# LNBF.net
KiCad netlist of a schematic drawn in Altium Designer
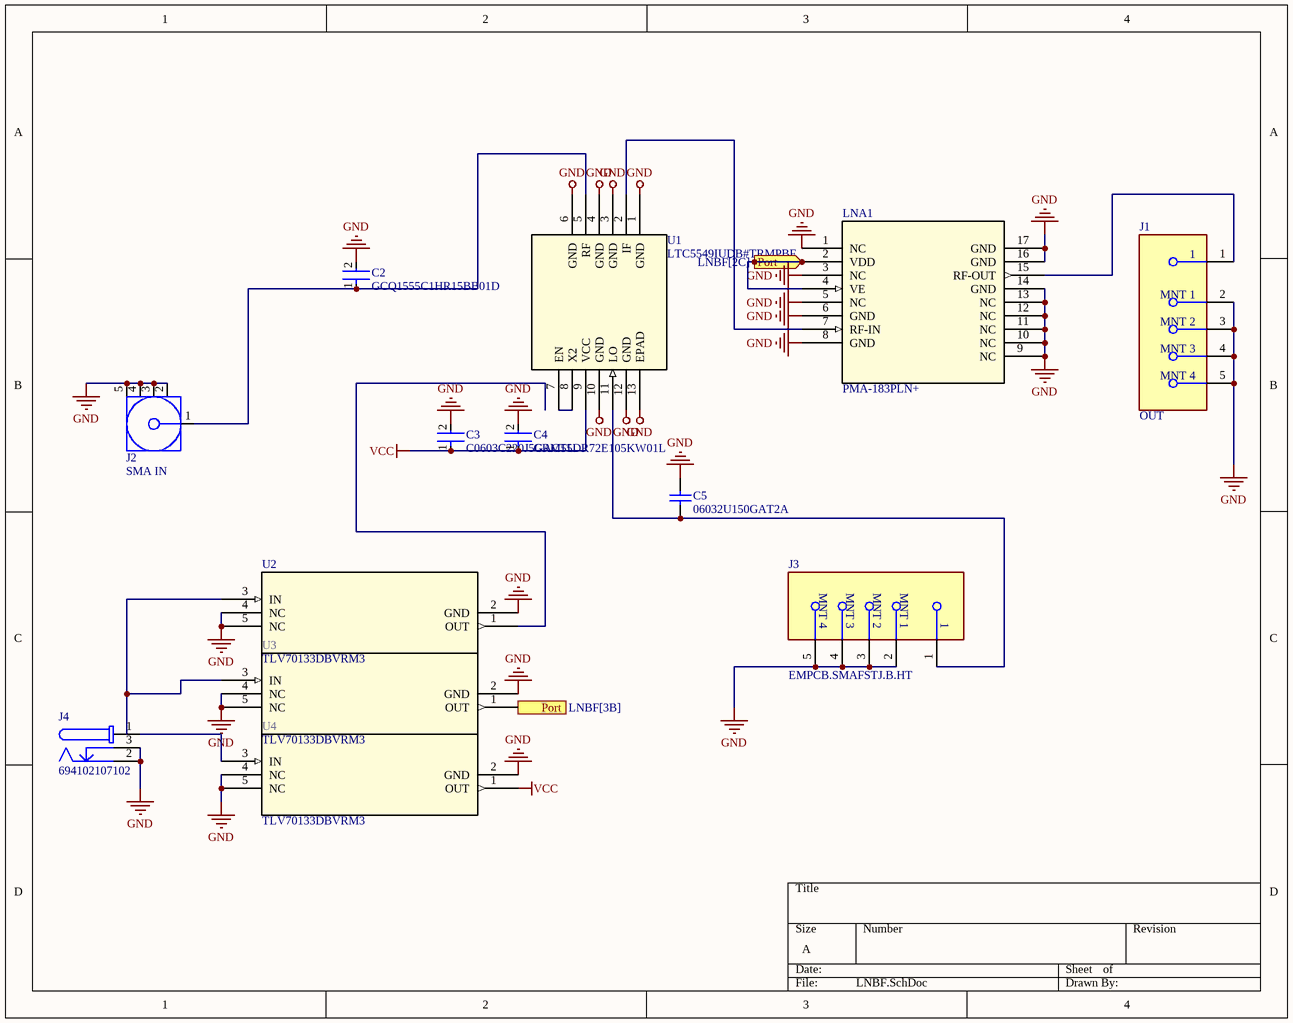
[diagram p0: LNBF.SchDoc]

(export (version "E")
  (design (tool "Eeschema 10.0.6"))
  (components
    (comp (ref "C2")
      (value "GCQ1555C1HR15BB01D")
      (footprint "FP-GCQ155-0_05-MFG")
      (description "High Q Ceramic Capacitor for Automotive 0.15pF ±0.1pF 50VDC C0G 0402 Paper T/R")
      (libsource (lib "Altium Content Vault") (part "02cd4be3c70576c341d710602a673aa"))
    )
    (comp (ref "C3")
      (value "C0603C220J5GACTU")
      (footprint "FP-C0603C-CF-MFG")
      (description "Cap Ceramic 22pF 50V C0G 5% SMD 0603 125°C Paper T/R")
      (fields (field (name "TOLERANCE") "0.05") (field (name "MANUFACTURER") "KEMET"))
      (libsource (lib "Altium Content Vault") (part "b4654b650e69147ec39a6b967a45e02"))
    )
    (comp (ref "C4")
      (value "GRM55DR72E105KW01L")
      (footprint "FP-GRM55D-0_4-IPC_A")
      (description "Chip Multilayer Ceramic Capacitors for General Purpose, 2220, 1.0uF, X7R, 15%, 10%, 250V")
      (fields (field (name "VOLTAGE") "250V") (field (name "TOLERANCE") "10%"))
      (libsource (lib "Altium Content Vault") (part "b4654b650e69147ec39a6b967a45e02"))
    )
    (comp (ref "C5")
      (value "06032U150GAT2A")
      (footprint "CAPC1508X91X25LL25T13")
      (fields (field (name "MANUFACTURER") "AVX Interconnect / Elco"))
      (libsource (lib "Altium Content Vault") (part "CAP"))
    )
    (comp (ref "J1")
      (value "OUT")
      (footprint "FP-EMPCB_SMAFSTJ_B_HT-MFG")
      (description "CONN SMA JACK STR 50OHM EDGE MNT")
      (fields
        (field (name "OCTOPART") "https://octopart.com/empcb.smafstj.b.ht-taoglas-24204431")
        (field (name "MANUFACTURER PART NUMBER") "EMPCB.SMAFSTJ.B.HT")
      )
      (libsource (lib "") (part "c65b8a639cdaef1819ea20b5466f8fa_1"))
    )
    (comp (ref "J2")
      (value "SMA IN")
      (footprint "MOLX-731000114_V")
      (description "SMA Right-Angle PCB Jack Receptacle, Brass Body, Gold Plated, 50 Ohm, 5-Pin THD, RoHS, Tray")
      (fields (field (name "MANUFACTURER") "Molex"))
      (libsource (lib "Altium Content Vault") (part "CN-S-4F-RF5"))
    )
    (comp (ref "J3")
      (value "EMPCB.SMAFSTJ.B.HT")
      (footprint "FP-EMPCB_SMAFSTJ_B_HT-MFG")
      (description "CONN SMA JACK STR 50OHM EDGE MNT")
      (fields
        (field (name "OCTOPART") "https://octopart.com/empcb.smafstj.b.ht-taoglas-24204431")
        (field (name "MANUFACTURER") "Taoglas Limited")
      )
      (libsource (lib "Altium Content Vault") (part "c65b8a639cdaef1819ea20b5466f8fa"))
    )
    (comp (ref "J4")
      (value "694102107102")
      (footprint "694102107102")
      (libsource (lib "Altium Content Vault") (part "DC Power Jack"))
    )
    (comp (ref "LNA1")
      (value "PMA-183PLN+")
      (footprint "JV2579_MNC")
      (description "No Description Available")
      (fields (field (name "COPYRIGHT") "Copyright (C) 2024 Ultra Librarian. All rights reserved."))
      (libsource (lib "PMA-183PLN&plus_") (part "PMA-183PLN+"))
    )
    (comp (ref "U1")
      (value "LTC5549IUDB#TRMPBF")
      (footprint "LTC5549IUDBTRMPBF_ADI")
      (description "No Description Available")
      (fields (field (name "COPYRIGHT") "Copyright (C) 2024 Ultra Librarian. All rights reserved."))
      (libsource (lib "LTC5549IUDBTRMPBF") (part "LTC5549IUDBTRMPBF"))
    )
    (comp (ref "U2")
      (value "TLV70133DBVRM3")
      (footprint "DBV5")
      (description "No Description Available")
      (fields (field (name "COPYRIGHT") "Copyright (C) 2024 Ultra Librarian. All rights reserved."))
      (libsource (lib "TLV70133DBVRM3") (part "TLV70133DBVRM3"))
    )
    (comp (ref "U3")
      (value "TLV70133DBVRM3")
      (footprint "DBV5")
      (description "No Description Available")
      (fields (field (name "COPYRIGHT") "Copyright (C) 2024 Ultra Librarian. All rights reserved."))
      (libsource (lib "TLV70133DBVRM3") (part "TLV70133DBVRM3"))
    )
    (comp (ref "U4")
      (value "TLV70133DBVRM3")
      (footprint "DBV5")
      (description "No Description Available")
      (fields (field (name "COPYRIGHT") "Copyright (C) 2024 Ultra Librarian. All rights reserved."))
      (libsource (lib "TLV70133DBVRM3") (part "TLV70133DBVRM3"))
    )
  )
  (nets
    (net (code "1") (name "/Port") (class "Default")
      (node (ref "LNA1") (pin "2") (pinfunction "VDD_2") (pintype "power_in"))
      (node (ref "LNA1") (pin "4") (pinfunction "VE_4") (pintype "input"))
      (node (ref "U3") (pin "1") (pinfunction "OUT_1") (pintype "output"))
    )
    (net (code "2") (name "GND") (class "Default")
      (node (ref "C2") (pin "2") (pinfunction "2_2") (pintype "passive"))
      (node (ref "C3") (pin "2") (pinfunction "2_2") (pintype "passive"))
      (node (ref "C4") (pin "2") (pinfunction "2_2") (pintype "passive"))
      (node (ref "C5") (pin "1") (pinfunction "1_1") (pintype "passive"))
      (node (ref "J1") (pin "2") (pinfunction "MNT_1_2") (pintype "passive"))
      (node (ref "J1") (pin "3") (pinfunction "MNT_2_3") (pintype "passive"))
      (node (ref "J1") (pin "4") (pinfunction "MNT_3_4") (pintype "passive"))
      (node (ref "J1") (pin "5") (pinfunction "MNT_4_5") (pintype "passive"))
      (node (ref "J2") (pin "2") (pinfunction "2_2") (pintype "passive"))
      (node (ref "J2") (pin "3") (pinfunction "3_3") (pintype "passive"))
      (node (ref "J2") (pin "4") (pinfunction "4_4") (pintype "passive"))
      (node (ref "J2") (pin "5") (pinfunction "5_5") (pintype "passive"))
      (node (ref "J3") (pin "2") (pinfunction "MNT_1_2") (pintype "passive"))
      (node (ref "J3") (pin "3") (pinfunction "MNT_2_3") (pintype "passive"))
      (node (ref "J3") (pin "4") (pinfunction "MNT_3_4") (pintype "passive"))
      (node (ref "J3") (pin "5") (pinfunction "MNT_4_5") (pintype "passive"))
      (node (ref "J4") (pin "2") (pinfunction "2_2") (pintype "passive"))
      (node (ref "J4") (pin "3") (pinfunction "3_3") (pintype "passive"))
      (node (ref "LNA1") (pin "1") (pinfunction "NC_1") (pintype "passive"))
      (node (ref "LNA1") (pin "10") (pinfunction "NC_10") (pintype "passive"))
      (node (ref "LNA1") (pin "11") (pinfunction "NC_11") (pintype "passive"))
      (node (ref "LNA1") (pin "12") (pinfunction "NC_12") (pintype "passive"))
      (node (ref "LNA1") (pin "13") (pinfunction "NC_13") (pintype "passive"))
      (node (ref "LNA1") (pin "14") (pinfunction "GND_14") (pintype "power_in"))
      (node (ref "LNA1") (pin "16") (pinfunction "GND_16") (pintype "power_in"))
      (node (ref "LNA1") (pin "17") (pinfunction "GND_17") (pintype "power_in"))
      (node (ref "LNA1") (pin "3") (pinfunction "NC_3") (pintype "passive"))
      (node (ref "LNA1") (pin "5") (pinfunction "NC_5") (pintype "passive"))
      (node (ref "LNA1") (pin "6") (pinfunction "GND_6") (pintype "power_in"))
      (node (ref "LNA1") (pin "8") (pinfunction "GND_8") (pintype "power_in"))
      (node (ref "LNA1") (pin "9") (pinfunction "NC_9") (pintype "passive"))
      (node (ref "U1") (pin "1") (pinfunction "GND_1") (pintype "power_in"))
      (node (ref "U1") (pin "10") (pinfunction "GND_10") (pintype "power_in"))
      (node (ref "U1") (pin "12") (pinfunction "GND_12") (pintype "power_in"))
      (node (ref "U1") (pin "13") (pinfunction "EPAD_13") (pintype "power_in"))
      (node (ref "U1") (pin "3") (pinfunction "GND_3") (pintype "power_in"))
      (node (ref "U1") (pin "4") (pinfunction "GND_4") (pintype "power_in"))
      (node (ref "U1") (pin "6") (pinfunction "GND_6") (pintype "power_in"))
      (node (ref "U2") (pin "2") (pinfunction "GND_2") (pintype "power_in"))
      (node (ref "U2") (pin "4") (pinfunction "NC_4") (pintype "passive"))
      (node (ref "U2") (pin "5") (pinfunction "NC_5") (pintype "passive"))
      (node (ref "U3") (pin "2") (pinfunction "GND_2") (pintype "power_in"))
      (node (ref "U3") (pin "4") (pinfunction "NC_4") (pintype "passive"))
      (node (ref "U3") (pin "5") (pinfunction "NC_5") (pintype "passive"))
      (node (ref "U4") (pin "2") (pinfunction "GND_2") (pintype "power_in"))
      (node (ref "U4") (pin "4") (pinfunction "NC_4") (pintype "passive"))
      (node (ref "U4") (pin "5") (pinfunction "NC_5") (pintype "passive"))
    )
    (net (code "3") (name "Net-(LNA1-RF-IN)") (class "Default")
      (node (ref "LNA1") (pin "7") (pinfunction "RF-IN_7") (pintype "input"))
      (node (ref "U1") (pin "2") (pinfunction "IF_2") (pintype "passive"))
    )
    (net (code "4") (name "Net-(LNA1-RF-OUT)") (class "Default")
      (node (ref "J1") (pin "1") (pinfunction "1_1") (pintype "passive"))
      (node (ref "LNA1") (pin "15") (pinfunction "RF-OUT_15") (pintype "output"))
    )
    (net (code "5") (name "Net-(U1-EN)") (class "Default")
      (node (ref "U1") (pin "7") (pinfunction "EN_7") (pintype "passive"))
      (node (ref "U1") (pin "8") (pinfunction "X2_8") (pintype "passive"))
    )
    (net (code "6") (name "Net-(U1-LO)") (class "Default")
      (node (ref "C5") (pin "2") (pinfunction "2_2") (pintype "passive"))
      (node (ref "J3") (pin "1") (pinfunction "1_1") (pintype "passive"))
      (node (ref "U1") (pin "11") (pinfunction "LO_11") (pintype "input"))
    )
    (net (code "7") (name "Net-(U1-RF)") (class "Default")
      (node (ref "C2") (pin "1") (pinfunction "1_1") (pintype "passive"))
      (node (ref "J2") (pin "1") (pinfunction "1_1") (pintype "passive"))
      (node (ref "U1") (pin "5") (pinfunction "RF_5") (pintype "passive"))
    )
    (net (code "8") (name "Net-(U2-IN)") (class "Default")
      (node (ref "U2") (pin "3") (pinfunction "IN_3") (pintype "input"))
      (node (ref "U3") (pin "3") (pinfunction "IN_3") (pintype "input"))
    )
    (net (code "9") (name "Net-(U4-IN)") (class "Default")
      (node (ref "J4") (pin "1") (pinfunction "1_1") (pintype "passive"))
      (node (ref "U4") (pin "3") (pinfunction "IN_3") (pintype "input"))
    )
    (net (code "10") (name "VCC") (class "Default")
      (node (ref "C3") (pin "1") (pinfunction "1_1") (pintype "passive"))
      (node (ref "C4") (pin "1") (pinfunction "1_1") (pintype "passive"))
      (node (ref "U1") (pin "9") (pinfunction "VCC_9") (pintype "power_in"))
      (node (ref "U4") (pin "1") (pinfunction "OUT_1") (pintype "output"))
    )
    (net (code "11") (name "unconnected-(U2-OUT-Pad1)") (class "Default")
      (node (ref "U2") (pin "1") (pinfunction "OUT_1") (pintype "output"))
    )
  )
)
